# Aux_HV_Board.net
KiCad netlist of a schematic drawn in Altium Designer
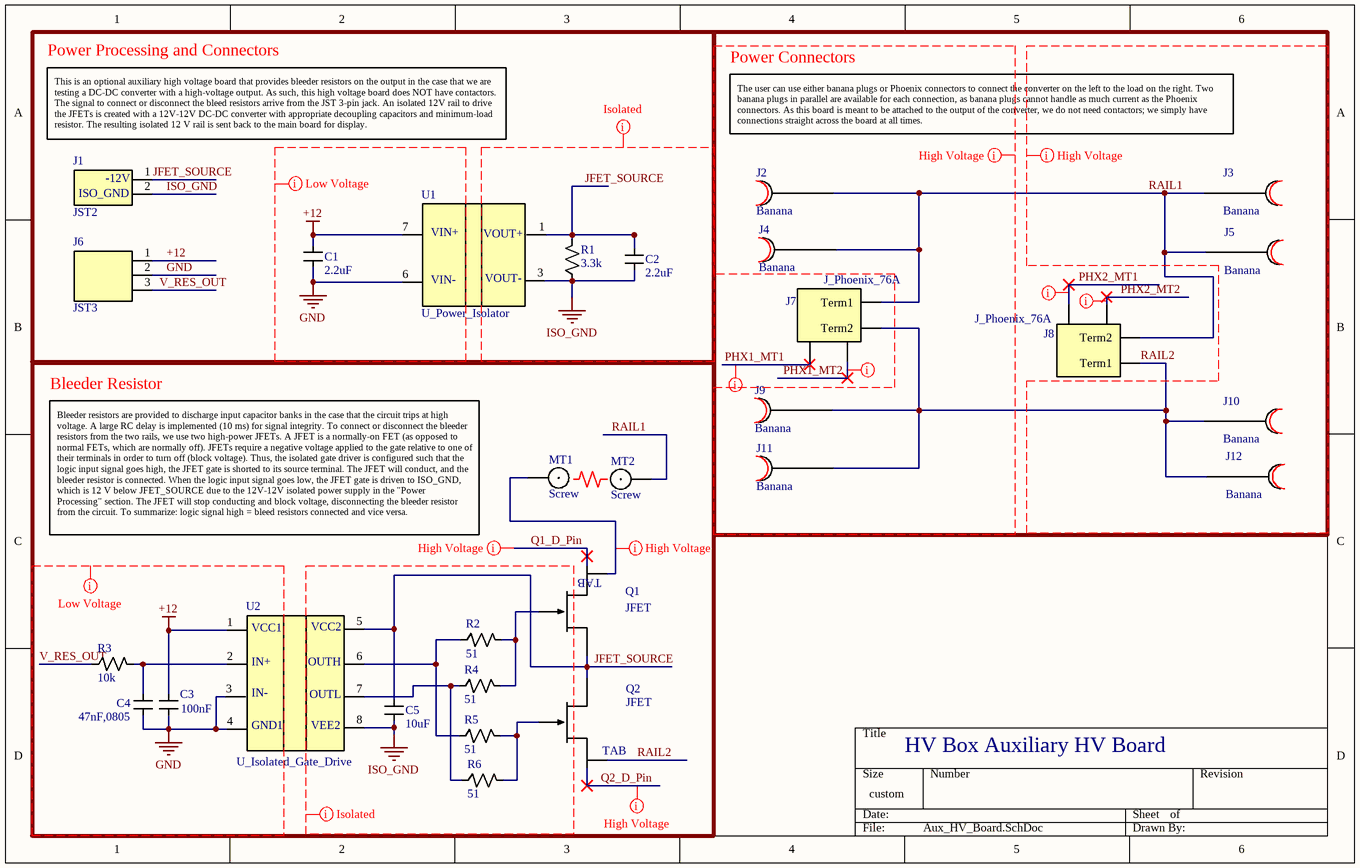
[diagram p0: Aux_HV_Board.SchDoc]

(export (version "E")
  (design (tool "Eeschema 10.0.6"))
  (components
    (comp (ref "C1")
      (value "2.2uF")
      (footprint "0603_CAP")
      (description "Capacitor SMD MLCC 2.2 uF 0603")
      (libsource (lib "Load_Bank_New_IntLib") (part "C_2.2uF_0603"))
    )
    (comp (ref "C2")
      (value "2.2uF")
      (footprint "0603_CAP")
      (description "Capacitor SMD MLCC 2.2 uF 0603")
      (libsource (lib "Load_Bank_New_IntLib") (part "C_2.2uF_0603"))
    )
    (comp (ref "C3")
      (value "100nF")
      (footprint "0603_CAP")
      (description "Capacitor SMD MLCC 100 nF 0603")
      (libsource (lib "Load_Bank_New_IntLib") (part "C_100nF_0603"))
    )
    (comp (ref "C4")
      (value "47nF,0805")
      (footprint "0805_CAP")
      (description "Capacitor SMD MLCC 47 nF 0805, C0G/NP0")
      (libsource (lib "HV_Box_IntLib") (part "C_47nF_0805"))
    )
    (comp (ref "C5")
      (value "10uF")
      (footprint "0805_CAP")
      (description "Capacitor SMD MLCC 10 uF 0805")
      (libsource (lib "Load_Bank_New_IntLib") (part "C_10uF_0805"))
    )
    (comp (ref "J1")
      (value "JST2")
      (footprint "JST_2")
      (description "Jack JST 2-pin")
      (libsource (lib "HV_Box_IntLib") (part "J_JST_2"))
    )
    (comp (ref "J2")
      (value "Banana")
      (footprint "BANANA_PLUG")
      (description "Banana Plug")
      (libsource (lib "HV_Box_IntLib") (part "J_Banana"))
    )
    (comp (ref "J3")
      (value "Banana")
      (footprint "BANANA_PLUG")
      (description "Banana Plug")
      (libsource (lib "HV_Box_IntLib") (part "J_Banana"))
    )
    (comp (ref "J4")
      (value "Banana")
      (footprint "BANANA_PLUG")
      (description "Banana Plug")
      (libsource (lib "HV_Box_IntLib") (part "J_Banana"))
    )
    (comp (ref "J5")
      (value "Banana")
      (footprint "BANANA_PLUG")
      (description "Banana Plug")
      (libsource (lib "HV_Box_IntLib") (part "J_Banana"))
    )
    (comp (ref "J6")
      (value "JST3")
      (footprint "JST_3")
      (description "Jack JST 3-pin")
      (libsource (lib "HV_Box_IntLib") (part "J_JST_3"))
    )
    (comp (ref "J7")
      (value "J_Phoenix_76A")
      (footprint "PHOENIX_CONNECTOR_76A")
      (description "Phoenix Connector, Female, 2 position, 76 A, 1 kV per position")
      (libsource (lib "HV_Box_IntLib") (part "J_Phoenix_76A"))
    )
    (comp (ref "J8")
      (value "J_Phoenix_76A")
      (footprint "PHOENIX_CONNECTOR_76A")
      (description "Phoenix Connector, Female, 2 position, 76 A, 1 kV per position")
      (libsource (lib "") (part "J_Phoenix_76A_1"))
    )
    (comp (ref "J9")
      (value "Banana")
      (footprint "BANANA_PLUG")
      (description "Banana Plug")
      (libsource (lib "HV_Box_IntLib") (part "J_Banana"))
    )
    (comp (ref "J10")
      (value "Banana")
      (footprint "BANANA_PLUG")
      (description "Banana Plug")
      (libsource (lib "HV_Box_IntLib") (part "J_Banana"))
    )
    (comp (ref "J11")
      (value "Banana")
      (footprint "BANANA_PLUG")
      (description "Banana Plug")
      (libsource (lib "HV_Box_IntLib") (part "J_Banana"))
    )
    (comp (ref "J12")
      (value "Banana")
      (footprint "BANANA_PLUG")
      (description "Banana Plug")
      (libsource (lib "HV_Box_IntLib") (part "J_Banana"))
    )
    (comp (ref "MT1")
      (value "Screw")
      (footprint "MOUNT_SMALL")
      (description "M5/M6 Screw Mount for connecting board to resistors")
      (libsource (lib "HV_Box_IntLib") (part "MT_Screw_Small"))
    )
    (comp (ref "MT2")
      (value "Screw")
      (footprint "MOUNT_SMALL")
      (description "M5/M6 Screw Mount for connecting board to resistors")
      (libsource (lib "HV_Box_IntLib") (part "MT_Screw_Small"))
    )
    (comp (ref "Q1")
      (value "JFET")
      (footprint "TO247")
      (description "N-Channel JFET1200 V 34 A TO 247-3")
      (libsource (lib "HV_Box_IntLib") (part "Q_JFET"))
    )
    (comp (ref "Q2")
      (value "JFET")
      (footprint "TO247")
      (description "N-Channel JFET1200 V 34 A TO 247-3")
      (libsource (lib "HV_Box_IntLib") (part "Q_JFET"))
    )
    (comp (ref "R1")
      (value "3.3k")
      (footprint "0603_RES")
      (description "Resistor 3.3 kOhm 0603 1%")
      (libsource (lib "Load_Bank_New_IntLib") (part "R_3300Ohm_0603_1%"))
    )
    (comp (ref "R2")
      (value "51")
      (footprint "0603_RES")
      (description "Resistor 51 Ohm 0603 1%")
      (libsource (lib "Load_Bank_New_IntLib") (part "R_51Ohm_0603_1%"))
    )
    (comp (ref "R3")
      (value "10k")
      (footprint "0603_RES")
      (description "Resistor 10 kOhm 0603 1%")
      (libsource (lib "Load_Bank_New_IntLib") (part "R_10kOhm_0603_1%"))
    )
    (comp (ref "R4")
      (value "51")
      (footprint "0603_RES")
      (description "Resistor 51 Ohm 0603 1%")
      (libsource (lib "Load_Bank_New_IntLib") (part "R_51Ohm_0603_1%"))
    )
    (comp (ref "R5")
      (value "51")
      (footprint "0603_RES")
      (description "Resistor 51 Ohm 0603 1%")
      (libsource (lib "Load_Bank_New_IntLib") (part "R_51Ohm_0603_1%"))
    )
    (comp (ref "R6")
      (value "51")
      (footprint "0603_RES")
      (description "Resistor 51 Ohm 0603 1%")
      (libsource (lib "Load_Bank_New_IntLib") (part "R_51Ohm_0603_1%"))
    )
    (comp (ref "U1")
      (value "U_Power_Isolator")
      (footprint "SIP7")
      (description "12 V -> 12 V DC-DC isolated converter, 84 mW output current, SIP7 4-lead package, 3 kV isolation")
      (libsource (lib "HV_Box_IntLib") (part "U_12_12_Power_Isolator"))
    )
    (comp (ref "U2")
      (value "U_Isolated_Gate_Drive")
      (footprint "GATE_DRIVER")
      (description "IC Isolated Gate Drive 3-15 V Output Supply Split Output")
      (libsource (lib "Load_Bank_New_IntLib") (part "U_Isolated_Gate_Drive"))
    )
  )
  (nets
    (net (code "1") (name "+12") (class "Default")
      (node (ref "C1") (pin "2") (pintype "passive"))
      (node (ref "C3") (pin "2") (pintype "passive"))
      (node (ref "J6") (pin "1") (pinfunction "Sig1_1") (pintype "passive"))
      (node (ref "U1") (pin "7") (pinfunction "Vin+_7") (pintype "passive"))
      (node (ref "U2") (pin "1") (pinfunction "VCC1_1") (pintype "passive"))
    )
    (net (code "2") (name "/JFET_SOURCE") (class "Default")
      (node (ref "C2") (pin "2") (pintype "passive"))
      (node (ref "C5") (pin "2") (pintype "passive"))
      (node (ref "J1") (pin "1") (pinfunction "Sig1_1") (pintype "passive"))
      (node (ref "Q1") (pin "3") (pinfunction "S_3") (pintype "passive"))
      (node (ref "Q2") (pin "3") (pinfunction "S_3") (pintype "passive"))
      (node (ref "R1") (pin "2") (pintype "passive"))
      (node (ref "U1") (pin "1") (pinfunction "VOUT+_1") (pintype "passive"))
      (node (ref "U2") (pin "5") (pinfunction "VCC2_5") (pintype "passive"))
    )
    (net (code "3") (name "/PHX1_MT1") (class "Default")
      (node (ref "J7") (pin "3") (pinfunction "Mt1_3") (pintype "passive+no_connect"))
    )
    (net (code "4") (name "/PHX1_MT2") (class "Default")
      (node (ref "J7") (pin "4") (pinfunction "Mt2_4") (pintype "passive+no_connect"))
    )
    (net (code "5") (name "/PHX2_MT1") (class "Default")
      (node (ref "J8") (pin "3") (pinfunction "Mt1_3") (pintype "passive+no_connect"))
    )
    (net (code "6") (name "/PHX2_MT2") (class "Default")
      (node (ref "J8") (pin "4") (pinfunction "Mt2_4") (pintype "passive+no_connect"))
    )
    (net (code "7") (name "/Q1_D_Pin") (class "Default")
      (node (ref "Q1") (pin "2") (pinfunction "D_2") (pintype "passive"))
    )
    (net (code "8") (name "/Q2_D_Pin") (class "Default")
      (node (ref "Q2") (pin "2") (pinfunction "D_2") (pintype "passive+no_connect"))
    )
    (net (code "9") (name "/RAIL1") (class "Default")
      (node (ref "J2") (pin "1") (pinfunction "Plug_1") (pintype "passive"))
      (node (ref "J3") (pin "1") (pinfunction "Plug_1") (pintype "passive"))
      (node (ref "J4") (pin "1") (pinfunction "Plug_1") (pintype "passive"))
      (node (ref "J5") (pin "1") (pinfunction "Plug_1") (pintype "passive"))
      (node (ref "J7") (pin "1") (pinfunction "Term1_1") (pintype "passive"))
      (node (ref "J8") (pin "2") (pinfunction "Term2_2") (pintype "passive"))
      (node (ref "MT2") (pin "1") (pintype "passive"))
    )
    (net (code "10") (name "/RAIL2") (class "Default")
      (node (ref "J10") (pin "1") (pinfunction "Plug_1") (pintype "passive"))
      (node (ref "J11") (pin "1") (pinfunction "Plug_1") (pintype "passive"))
      (node (ref "J12") (pin "1") (pinfunction "Plug_1") (pintype "passive"))
      (node (ref "J7") (pin "2") (pinfunction "Term2_2") (pintype "passive"))
      (node (ref "J8") (pin "1") (pinfunction "Term1_1") (pintype "passive"))
      (node (ref "J9") (pin "1") (pinfunction "Plug_1") (pintype "passive"))
      (node (ref "Q2") (pin "4") (pinfunction "TAB_4") (pintype "passive"))
    )
    (net (code "11") (name "/V_RES_OUT") (class "Default")
      (node (ref "J6") (pin "3") (pinfunction "NC_3") (pintype "passive"))
      (node (ref "R3") (pin "1") (pintype "passive"))
    )
    (net (code "12") (name "GND") (class "Default")
      (node (ref "C1") (pin "1") (pintype "passive"))
      (node (ref "C3") (pin "1") (pintype "passive"))
      (node (ref "C4") (pin "1") (pintype "passive"))
      (node (ref "J6") (pin "2") (pinfunction "Sig2_2") (pintype "passive"))
      (node (ref "U1") (pin "6") (pinfunction "VIN-_6") (pintype "passive"))
      (node (ref "U2") (pin "3") (pinfunction "IN-_3") (pintype "passive"))
      (node (ref "U2") (pin "4") (pinfunction "GND1_4") (pintype "passive"))
    )
    (net (code "13") (name "ISO_GND") (class "Default")
      (node (ref "C2") (pin "1") (pintype "passive"))
      (node (ref "C5") (pin "1") (pintype "passive"))
      (node (ref "J1") (pin "2") (pinfunction "Sig2_2") (pintype "passive"))
      (node (ref "R1") (pin "1") (pintype "passive"))
      (node (ref "U1") (pin "3") (pinfunction "VOUT-_3") (pintype "passive"))
      (node (ref "U2") (pin "8") (pinfunction "VEE2_8") (pintype "passive"))
    )
    (net (code "14") (name "Net-(Q1-G)") (class "Default")
      (node (ref "Q1") (pin "1") (pinfunction "G_1") (pintype "passive"))
      (node (ref "R2") (pin "2") (pintype "passive"))
      (node (ref "R4") (pin "2") (pintype "passive"))
    )
    (net (code "15") (name "Net-(Q1-TAB)") (class "Default")
      (node (ref "MT1") (pin "1") (pintype "passive"))
      (node (ref "Q1") (pin "4") (pinfunction "TAB_4") (pintype "passive"))
    )
    (net (code "16") (name "Net-(Q2-G)") (class "Default")
      (node (ref "Q2") (pin "1") (pinfunction "G_1") (pintype "passive"))
      (node (ref "R5") (pin "2") (pintype "passive"))
      (node (ref "R6") (pin "2") (pintype "passive"))
    )
    (net (code "17") (name "Net-(U2-IN+)") (class "Default")
      (node (ref "C4") (pin "2") (pintype "passive"))
      (node (ref "R3") (pin "2") (pintype "passive"))
      (node (ref "U2") (pin "2") (pinfunction "IN+_2") (pintype "passive"))
    )
    (net (code "18") (name "Net-(U2-OUTH)") (class "Default")
      (node (ref "R2") (pin "1") (pintype "passive"))
      (node (ref "R5") (pin "1") (pintype "passive"))
      (node (ref "U2") (pin "6") (pinfunction "OUTH_6") (pintype "passive"))
    )
    (net (code "19") (name "Net-(U2-OUTL)") (class "Default")
      (node (ref "R4") (pin "1") (pintype "passive"))
      (node (ref "R6") (pin "1") (pintype "passive"))
      (node (ref "U2") (pin "7") (pinfunction "OUTL_7") (pintype "passive"))
    )
  )
)
